# POWER.net
KiCad netlist of a schematic drawn in Altium Designer
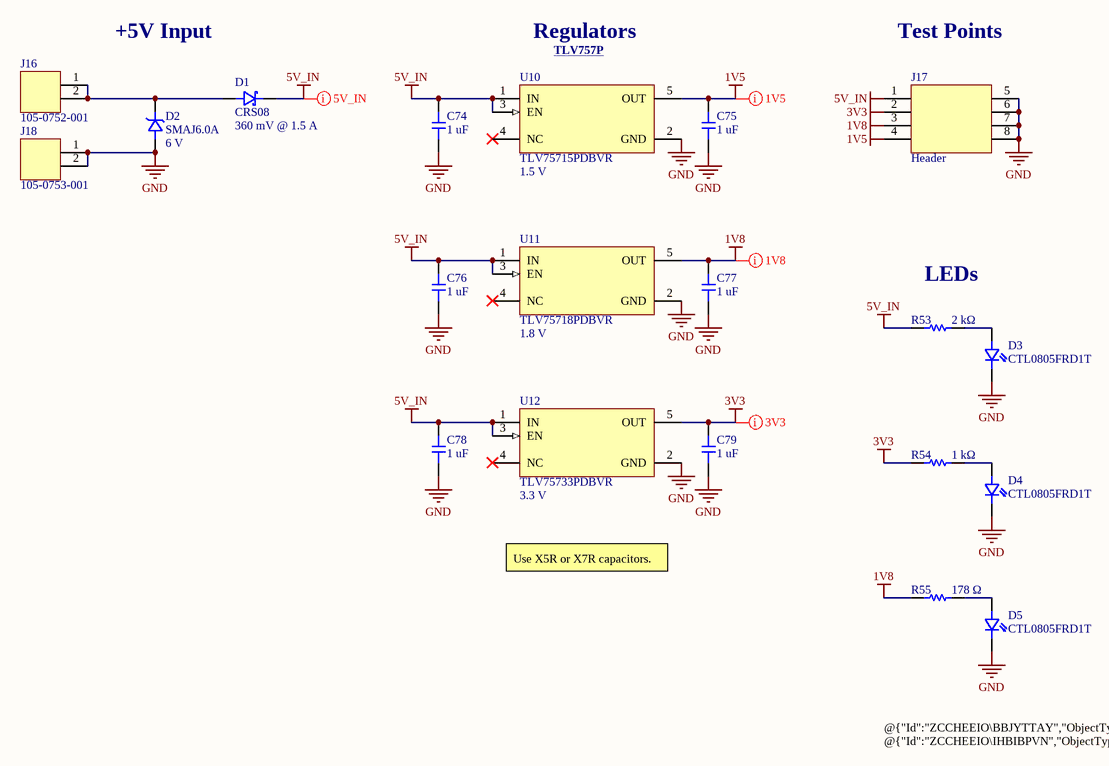
[diagram p0: POWER.SchDoc]

(export (version "E")
  (design (tool "Eeschema 10.0.6"))
  (components
    (comp (ref "C74")
      (value "1 uF")
      (footprint "CAP_0805")
      (description "50V 1uF X7R ±10% 0805 Multilayer Ceramic Capacitors MLCC - SMD/SMT ROHS")
      (fields
        (field (name "MANUFACTURER") "Samsung Electro-Mechanics")
        (field (name "MANUFACTURER PART NUMBER") "CL21B105KBFNNNE")
      )
      (libsource (lib "Titan") (part "CAP"))
    )
    (comp (ref "C75")
      (value "1 uF")
      (footprint "CAP_0805")
      (description "50V 1uF X7R ±10% 0805 Multilayer Ceramic Capacitors MLCC - SMD/SMT ROHS")
      (fields
        (field (name "MANUFACTURER") "Samsung Electro-Mechanics")
        (field (name "MANUFACTURER PART NUMBER") "CL21B105KBFNNNE")
      )
      (libsource (lib "Titan") (part "CAP"))
    )
    (comp (ref "C76")
      (value "1 uF")
      (footprint "CAP_0805")
      (description "50V 1uF X7R ±10% 0805 Multilayer Ceramic Capacitors MLCC - SMD/SMT ROHS")
      (fields
        (field (name "MANUFACTURER") "Samsung Electro-Mechanics")
        (field (name "MANUFACTURER PART NUMBER") "CL21B105KBFNNNE")
      )
      (libsource (lib "Titan") (part "CAP"))
    )
    (comp (ref "C77")
      (value "1 uF")
      (footprint "CAP_0805")
      (description "50V 1uF X7R ±10% 0805 Multilayer Ceramic Capacitors MLCC - SMD/SMT ROHS")
      (fields
        (field (name "MANUFACTURER") "Samsung Electro-Mechanics")
        (field (name "MANUFACTURER PART NUMBER") "CL21B105KBFNNNE")
      )
      (libsource (lib "Titan") (part "CAP"))
    )
    (comp (ref "C78")
      (value "1 uF")
      (footprint "CAP_0805")
      (description "50V 1uF X7R ±10% 0805 Multilayer Ceramic Capacitors MLCC - SMD/SMT ROHS")
      (fields
        (field (name "MANUFACTURER") "Samsung Electro-Mechanics")
        (field (name "MANUFACTURER PART NUMBER") "CL21B105KBFNNNE")
      )
      (libsource (lib "Titan") (part "CAP"))
    )
    (comp (ref "C79")
      (value "1 uF")
      (footprint "CAP_0805")
      (description "50V 1uF X7R ±10% 0805 Multilayer Ceramic Capacitors MLCC - SMD/SMT ROHS")
      (fields
        (field (name "MANUFACTURER") "Samsung Electro-Mechanics")
        (field (name "MANUFACTURER PART NUMBER") "CL21B105KBFNNNE")
      )
      (libsource (lib "Titan") (part "CAP"))
    )
    (comp (ref "D1")
      (value "CRS08")
      (footprint "CRS08")
      (description "Rectifier Diode, Schottky, 1 Phase, 1 Element, 1.5A, 30V V(RRM)")
      (fields
        (field (name "MANUFACTURER") "Toshiba Semiconductor and Storage")
        (field (name "MANUFACTURER PART NUMBER") "CRS08(TE85L,Q,M)")
        (field (name "FORWARD VOLTAGE") "360 mV @ 1.5 A")
      )
      (libsource (lib "Titan") (part "CRS08"))
    )
    (comp (ref "D2")
      (value "SMAJ6.0A")
      (footprint "SMAJ")
      (description "SMAJ Series 10.3 V 0.4 kW Surface Mount Uni-Directional TVS Diode - DO-214AC")
      (fields
        (field (name "MANUFACTURER") "Littelfuse Inc.")
        (field (name "REVERSE STANDOFF VOLTAGE") "6 V")
        (field (name "VOLTAGE") "60V")
      )
      (libsource (lib "Titan") (part "SMAJ6.0A"))
    )
    (comp (ref "D3")
      (value "CTL0805FRD1T")
      (footprint "CTL0805FRD1T")
      (description "Chip Type LED, 0805, Flat Lens, Red")
      (fields
        (field (name "MANUFACTURER") "Venkel")
        (field (name "MANUFACTURER PART NUMBER") "CTL0805FRD1T-CT")
      )
      (libsource (lib "Titan") (part "CTL0805FRD1T"))
    )
    (comp (ref "D4")
      (value "CTL0805FRD1T")
      (footprint "CTL0805FRD1T")
      (description "Chip Type LED, 0805, Flat Lens, Red")
      (fields
        (field (name "MANUFACTURER") "Venkel")
        (field (name "MANUFACTURER PART NUMBER") "CTL0805FRD1T-CT")
      )
      (libsource (lib "Titan") (part "CTL0805FRD1T"))
    )
    (comp (ref "D5")
      (value "CTL0805FRD1T")
      (footprint "CTL0805FRD1T")
      (description "Chip Type LED, 0805, Flat Lens, Red")
      (fields
        (field (name "MANUFACTURER") "Venkel")
        (field (name "MANUFACTURER PART NUMBER") "CTL0805FRD1T-CT")
      )
      (libsource (lib "Titan") (part "CTL0805FRD1T"))
    )
    (comp (ref "J16")
      (value "105-0752-001")
      (footprint "CONN_BANANA_JACK")
      (description "Red Tip Jack Standard Horizontal Pcb Mount For Diameter .080 Plug")
      (fields (field (name "MANUFACTURER") "Cinch Connectivity Solutions Johnson"))
      (libsource (lib "Titan") (part "105-0752-001"))
    )
    (comp (ref "J17")
      (value "Header")
      (footprint "CONN_2x4_2.54mm_PinHeader_Vertical")
      (description "Pin Header, Board-to-Board, 2.54 mm, 2 Rows, 8 Contacts, Through Hole, TSW Series")
      (fields
        (field (name "MANUFACTURER") "Samtec")
        (field (name "MANUFACTURER PART NUMBER") "TSW-104-07-F-D")
      )
      (libsource (lib "Titan") (part "CONN_2x4_2.54mm_PinHeader_Vertical"))
    )
    (comp (ref "J18")
      (value "105-0753-001")
      (footprint "CONN_BANANA_JACK")
      (description "Test Jack, 2mm Diameter Standard Tip Plugs, 5 A, 1.32 mm, 1.5 kV, Black")
      (fields (field (name "MANUFACTURER") "Cinch Connectivity Solutions Johnson"))
      (libsource (lib "Titan") (part "105-0753-001"))
    )
    (comp (ref "R53")
      (value "2 kΩ")
      (footprint "RES_0603")
      (description "100Mw Thick Film Resistors 100Ppm/ 1% 2K 0603 Chip Resistor Surface Mount Rohs")
      (fields
        (field (name "MANUFACTURER") "Yageo")
        (field (name "MANUFACTURER PART NUMBER") "RC0603FR-072KL")
      )
      (libsource (lib "Titan") (part "RES"))
    )
    (comp (ref "R54")
      (value "1 kΩ")
      (footprint "RES_0603")
      (description "100mW Thick Film Resistors 75V ±100ppm/℃ ±1% 1kΩ 0603 Chip Resistor - Surface Mount ROHS")
      (fields
        (field (name "MANUFACTURER") "Yageo")
        (field (name "MANUFACTURER PART NUMBER") "RC0603FR-071KL")
      )
      (libsource (lib "Titan") (part "RES"))
    )
    (comp (ref "R55")
      (value "178 Ω")
      (footprint "RES_0603")
      (description "Res Thick Film 0603 178 Ohm 1% 0.1W(1/10W) ±100ppm/C Pad SMD T/R")
      (fields
        (field (name "MANUFACTURER") "Yageo")
        (field (name "MANUFACTURER PART NUMBER") "RC0603FR-07178RL")
      )
      (libsource (lib "Titan") (part "RES"))
    )
    (comp (ref "U10")
      (value "TLV75715PDBVR")
      (footprint "TLV757XXPDBVR")
      (description "1-A, low-IQ high-accuracy low-dropout (LDO) voltage regulator with enable 5-SOT-23 -40 to 125")
      (fields (field (name "MANUFACTURER") "Texas Instruments") (field (name "OUTPUT VOLTAGE") "1.5 V"))
      (libsource (lib "Titan") (part "TLV75715PDBVR"))
    )
    (comp (ref "U11")
      (value "TLV75718PDBVR")
      (footprint "TLV757XXPDBVR")
      (description "1-A, low-IQ high-accuracy low-dropout (LDO) voltage regulator with enable 5-SOT-23 -40 to 125")
      (fields (field (name "MANUFACTURER") "Texas Instruments") (field (name "OUTPUT VOLTAGE") "1.8 V"))
      (libsource (lib "Titan") (part "TLV75718PDBVR"))
    )
    (comp (ref "U12")
      (value "TLV75733PDBVR")
      (footprint "TLV757XXPDBVR")
      (description "1-A, low-IQ high-accuracy low-dropout (LDO) voltage regulator with enable 5-SOT-23 -40 to 125")
      (fields (field (name "MANUFACTURER") "Texas Instruments") (field (name "OUTPUT VOLTAGE") "3.3 V"))
      (libsource (lib "Titan") (part "TLV75733PDBVR"))
    )
  )
  (nets
    (net (code "1") (name "1V5") (class "Default")
      (node (ref "C75") (pin "2") (pintype "passive"))
      (node (ref "J17") (pin "4") (pintype "passive"))
      (node (ref "U10") (pin "5") (pinfunction "OUT_5") (pintype "power_in"))
    )
    (net (code "2") (name "1V8") (class "Default")
      (node (ref "C77") (pin "2") (pintype "passive"))
      (node (ref "J17") (pin "3") (pintype "passive"))
      (node (ref "R55") (pin "1") (pintype "passive"))
      (node (ref "U11") (pin "5") (pinfunction "OUT_5") (pintype "power_in"))
    )
    (net (code "3") (name "3V3") (class "Default")
      (node (ref "C79") (pin "2") (pintype "passive"))
      (node (ref "J17") (pin "2") (pintype "passive"))
      (node (ref "R54") (pin "1") (pintype "passive"))
      (node (ref "U12") (pin "5") (pinfunction "OUT_5") (pintype "power_in"))
    )
    (net (code "4") (name "5V_IN") (class "Default")
      (node (ref "C74") (pin "2") (pintype "passive"))
      (node (ref "C76") (pin "2") (pintype "passive"))
      (node (ref "C78") (pin "2") (pintype "passive"))
      (node (ref "D1") (pin "2") (pintype "passive"))
      (node (ref "J17") (pin "1") (pintype "passive"))
      (node (ref "R53") (pin "1") (pintype "passive"))
      (node (ref "U10") (pin "1") (pinfunction "IN_1") (pintype "power_in"))
      (node (ref "U10") (pin "3") (pinfunction "EN_3") (pintype "input"))
      (node (ref "U11") (pin "1") (pinfunction "IN_1") (pintype "power_in"))
      (node (ref "U11") (pin "3") (pinfunction "EN_3") (pintype "input"))
      (node (ref "U12") (pin "1") (pinfunction "IN_1") (pintype "power_in"))
      (node (ref "U12") (pin "3") (pinfunction "EN_3") (pintype "input"))
    )
    (net (code "5") (name "GND") (class "Default")
      (node (ref "C74") (pin "1") (pintype "passive"))
      (node (ref "C75") (pin "1") (pintype "passive"))
      (node (ref "C76") (pin "1") (pintype "passive"))
      (node (ref "C77") (pin "1") (pintype "passive"))
      (node (ref "C78") (pin "1") (pintype "passive"))
      (node (ref "C79") (pin "1") (pintype "passive"))
      (node (ref "D2") (pin "1") (pintype "passive"))
      (node (ref "D3") (pin "2") (pintype "passive"))
      (node (ref "D4") (pin "2") (pintype "passive"))
      (node (ref "D5") (pin "2") (pintype "passive"))
      (node (ref "J17") (pin "5") (pintype "passive"))
      (node (ref "J17") (pin "6") (pintype "passive"))
      (node (ref "J17") (pin "7") (pintype "passive"))
      (node (ref "J17") (pin "8") (pintype "passive"))
      (node (ref "J18") (pin "1") (pintype "power_in"))
      (node (ref "J18") (pin "2") (pintype "power_in"))
      (node (ref "U10") (pin "2") (pinfunction "GND_2") (pintype "power_in"))
      (node (ref "U11") (pin "2") (pinfunction "GND_2") (pintype "power_in"))
      (node (ref "U12") (pin "2") (pinfunction "GND_2") (pintype "power_in"))
    )
    (net (code "6") (name "Net-(D1-Pad1)") (class "Default")
      (node (ref "D1") (pin "1") (pintype "passive"))
      (node (ref "D2") (pin "2") (pintype "passive"))
      (node (ref "J16") (pin "1") (pintype "power_in"))
      (node (ref "J16") (pin "2") (pintype "power_in"))
    )
    (net (code "7") (name "Net-(D3-Pad1)") (class "Default")
      (node (ref "D3") (pin "1") (pintype "passive"))
      (node (ref "R53") (pin "2") (pintype "passive"))
    )
    (net (code "8") (name "Net-(D4-Pad1)") (class "Default")
      (node (ref "D4") (pin "1") (pintype "passive"))
      (node (ref "R54") (pin "2") (pintype "passive"))
    )
    (net (code "9") (name "Net-(D5-Pad1)") (class "Default")
      (node (ref "D5") (pin "1") (pintype "passive"))
      (node (ref "R55") (pin "2") (pintype "passive"))
    )
    (net (code "10") (name "unconnected-(U10-NC-Pad4)") (class "Default")
      (node (ref "U10") (pin "4") (pinfunction "NC_4") (pintype "passive+no_connect"))
    )
    (net (code "11") (name "unconnected-(U11-NC-Pad4)") (class "Default")
      (node (ref "U11") (pin "4") (pinfunction "NC_4") (pintype "passive+no_connect"))
    )
    (net (code "12") (name "unconnected-(U12-NC-Pad4)") (class "Default")
      (node (ref "U12") (pin "4") (pinfunction "NC_4") (pintype "passive+no_connect"))
    )
  )
)
